# fp_usb2_ba.net
KiCad netlist of a schematic drawn in EAGLE
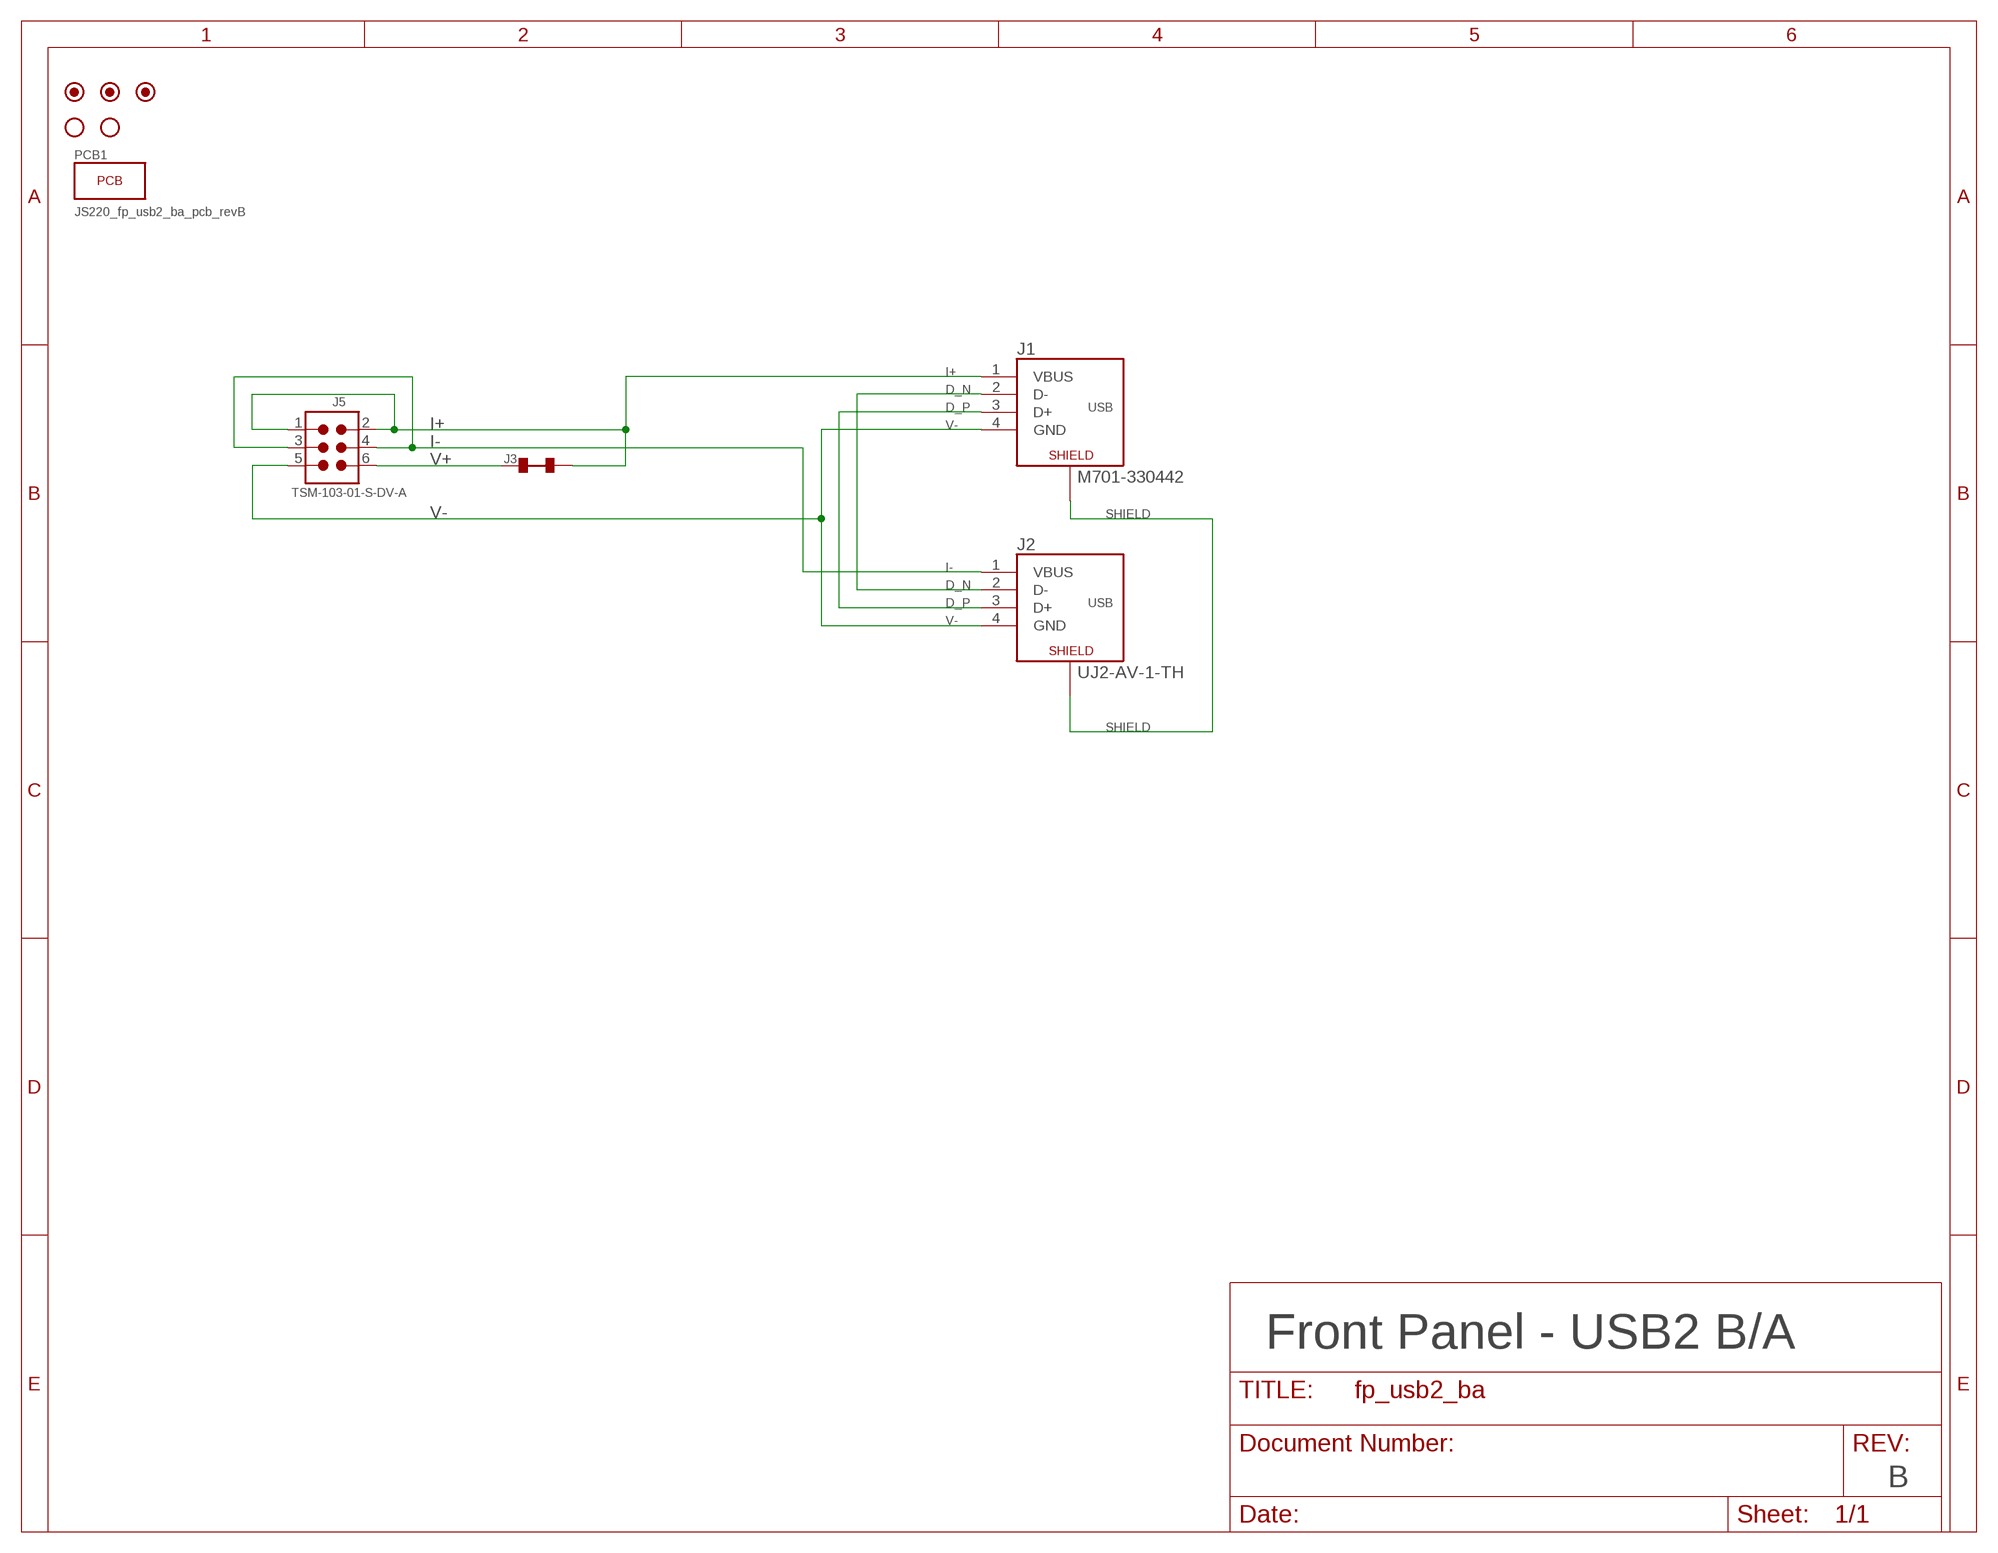
[diagram p0: schematic, sheet 1]

(export (version "E")
  (design (tool "Eeschema 10.0.6"))
  (components
    (comp (ref "FUD1")
      (value "FIDUCIAL_1MM")
      (footprint "eagle-import:FIDUCIAL_1MM_2MM")
      (libsource (lib "eagle-import") (part "FIDUCIAL_1MM"))
    )
    (comp (ref "FUD2")
      (value "FIDUCIAL_1MM")
      (footprint "eagle-import:FIDUCIAL_1MM_2MM")
      (libsource (lib "eagle-import") (part "FIDUCIAL_1MM"))
    )
    (comp (ref "FUD3")
      (value "FIDUCIAL_1MM")
      (footprint "eagle-import:FIDUCIAL_1MM_2MM")
      (libsource (lib "eagle-import") (part "FIDUCIAL_1MM"))
    )
    (comp (ref "H1")
      (value "HOLE_#6_NORESTRICT")
      (footprint "eagle-import:HOLE_3.5MM_NORESTRICT")
      (libsource (lib "eagle-import") (part "HOLE_#6_NORESTRICT"))
    )
    (comp (ref "H2")
      (value "HOLE_#6_NORESTRICT")
      (footprint "eagle-import:HOLE_3.5MM_NORESTRICT")
      (libsource (lib "eagle-import") (part "HOLE_#6_NORESTRICT"))
    )
    (comp (ref "J1")
      (value "M701-330442")
      (footprint "eagle-import:USB-B-VTH")
      (libsource (lib "eagle-import") (part "USB-4-B_VTH"))
    )
    (comp (ref "J2")
      (value "UJ2-AV-1-TH")
      (footprint "eagle-import:USB-A-VTH")
      (libsource (lib "eagle-import") (part "USB-4-A_VTH"))
    )
    (comp (ref "J3")
      (value "TRACE_CUT0603")
      (footprint "eagle-import:J0603")
      (libsource (lib "eagle-import") (part "TRACE_CUT0603"))
    )
    (comp (ref "J5")
      (value "TSM-103-01-S-DV-A")
      (footprint "eagle-import:CONN_0.1_3X2_MSA")
      (libsource (lib "eagle-import") (part "CONN_0.1_3X2_MSA"))
    )
  )
  (nets
    (net (code "1") (name "/D_N") (class "Default")
      (node (ref "J1") (pin "2") (pinfunction "D-_2") (pintype "bidirectional"))
      (node (ref "J2") (pin "2") (pinfunction "D-_2") (pintype "bidirectional"))
    )
    (net (code "2") (name "/D_P") (class "Default")
      (node (ref "J1") (pin "3") (pinfunction "D+_3") (pintype "bidirectional"))
      (node (ref "J2") (pin "3") (pinfunction "D+_3") (pintype "bidirectional"))
    )
    (net (code "3") (name "/I+") (class "Default")
      (node (ref "J1") (pin "1") (pinfunction "VBUS_1") (pintype "bidirectional"))
      (node (ref "J3") (pin "2") (pinfunction "P$2_2") (pintype "bidirectional"))
      (node (ref "J5") (pin "1") (pinfunction "1_1") (pintype "bidirectional"))
      (node (ref "J5") (pin "2") (pinfunction "2_2") (pintype "bidirectional"))
    )
    (net (code "4") (name "/I-") (class "Default")
      (node (ref "J2") (pin "1") (pinfunction "VBUS_1") (pintype "bidirectional"))
      (node (ref "J5") (pin "3") (pinfunction "3_3") (pintype "bidirectional"))
      (node (ref "J5") (pin "4") (pinfunction "4_4") (pintype "bidirectional"))
    )
    (net (code "5") (name "/SHIELD") (class "Default")
      (node (ref "J1") (pin "SHIELD@1") (pinfunction "SHIELD_SHIELD@1") (pintype "bidirectional"))
      (node (ref "J1") (pin "SHIELD@3") (pinfunction "SHIELD_SHIELD@3") (pintype "bidirectional"))
      (node (ref "J2") (pin "SHIELD@1") (pinfunction "SHIELD_SHIELD@1") (pintype "bidirectional"))
      (node (ref "J2") (pin "SHIELD@3") (pinfunction "SHIELD_SHIELD@3") (pintype "bidirectional"))
    )
    (net (code "6") (name "/V+") (class "Default")
      (node (ref "J3") (pin "1") (pinfunction "P$1_1") (pintype "bidirectional"))
      (node (ref "J5") (pin "6") (pinfunction "6_6") (pintype "bidirectional"))
    )
    (net (code "7") (name "/V-") (class "Default")
      (node (ref "J1") (pin "4") (pinfunction "GND_4") (pintype "bidirectional"))
      (node (ref "J2") (pin "4") (pinfunction "GND_4") (pintype "bidirectional"))
      (node (ref "J5") (pin "5") (pinfunction "5_5") (pintype "bidirectional"))
    )
  )
)
